# STorM32_NT_splitter_v10.net
KiCad netlist of a schematic drawn in EAGLE
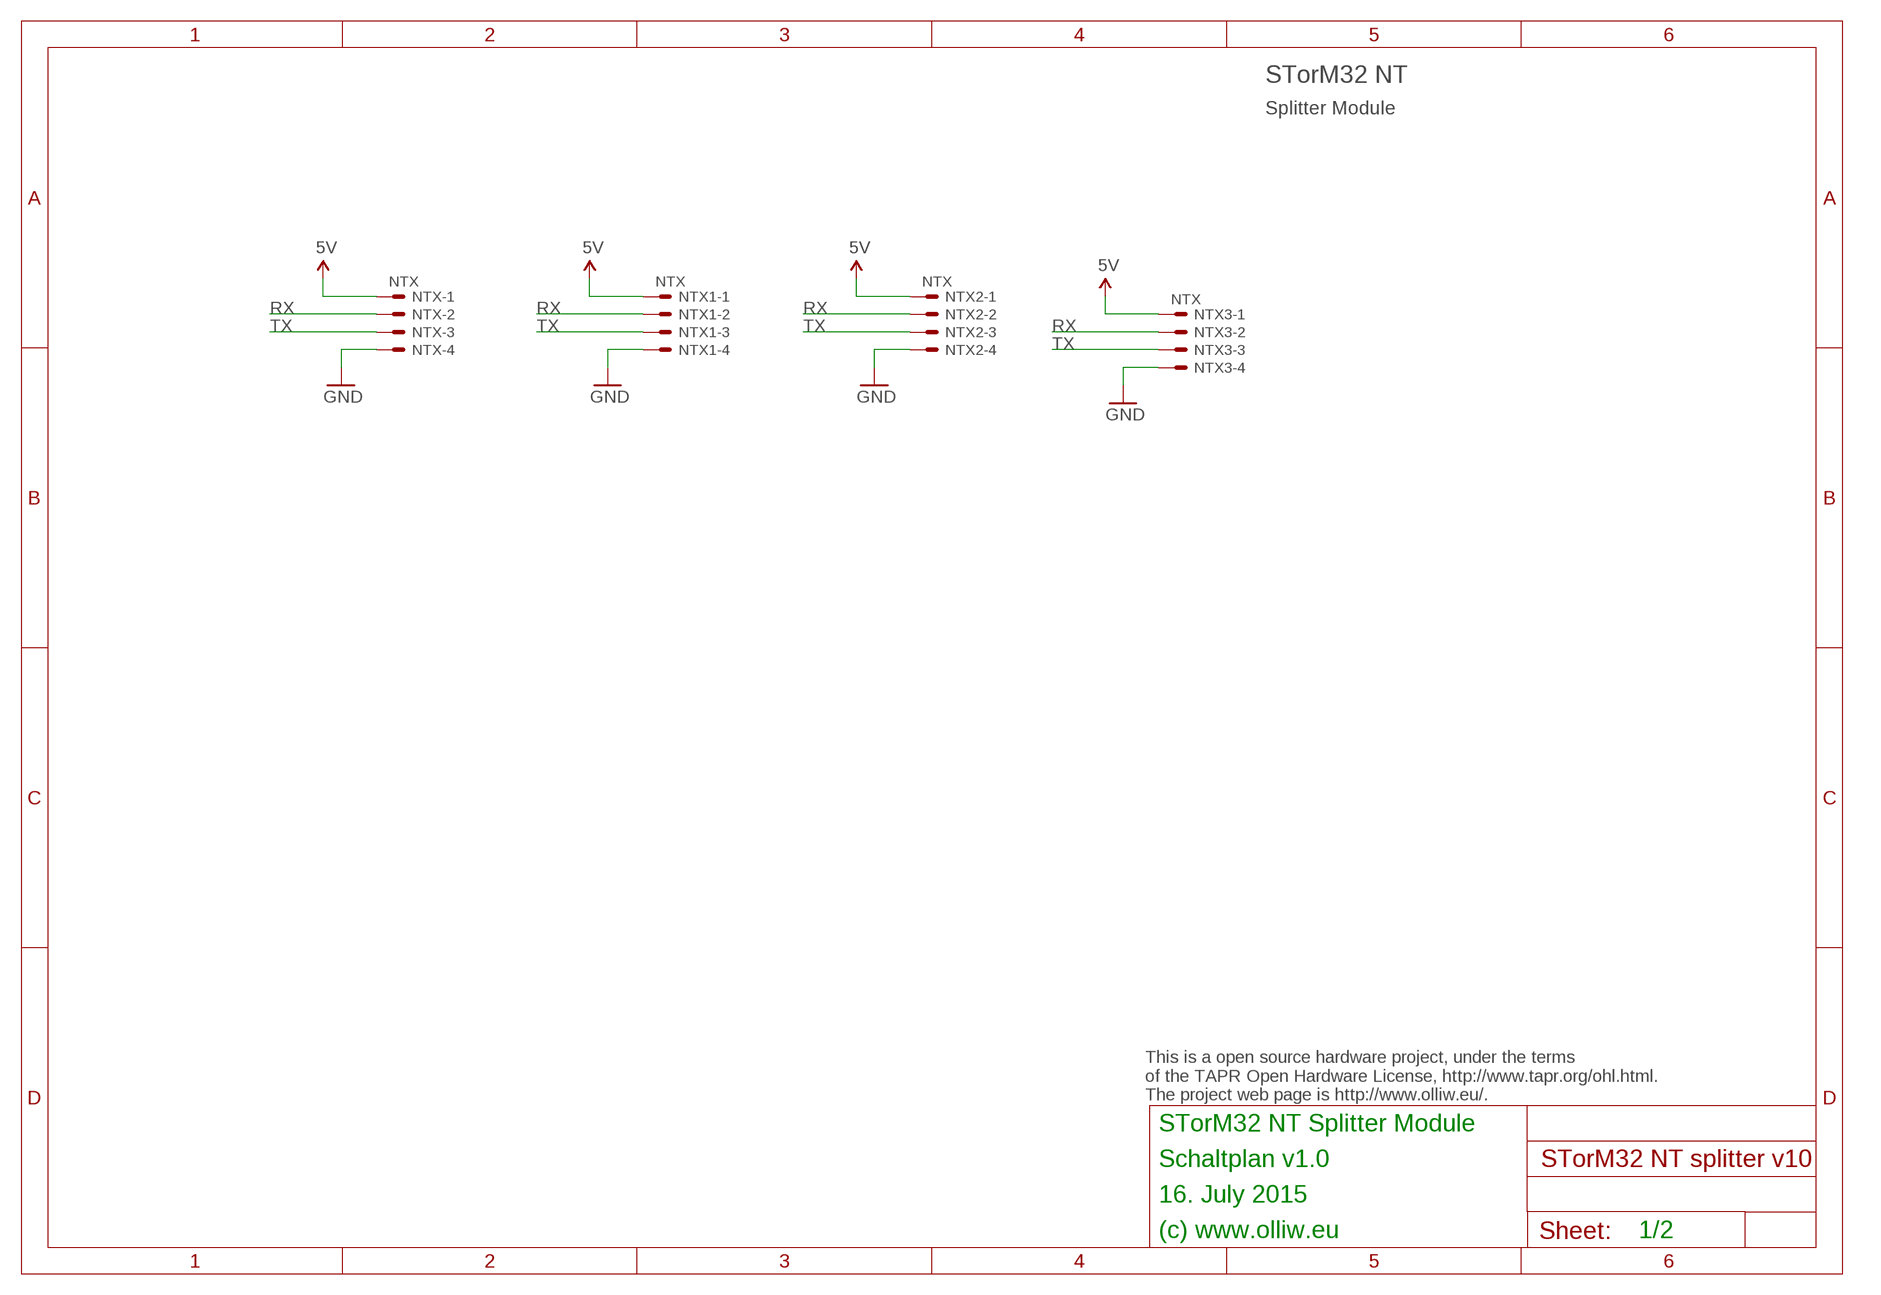
[diagram p0: schematic, sheet 1]

(export (version "E")
  (design (tool "Eeschema 10.0.6"))
  (components
    (comp (ref "NTX")
      (value "NTX")
      (footprint "eagle-import:SM04B-SRSS-TB")
      (libsource (lib "eagle-import") (part "?M04B-SRSS-TBS"))
    )
    (comp (ref "NTX1")
      (value "NTX")
      (footprint "eagle-import:SM04B-SRSS-TB")
      (libsource (lib "eagle-import") (part "?M04B-SRSS-TBS"))
    )
    (comp (ref "NTX2")
      (value "NTX")
      (footprint "eagle-import:SM04B-SRSS-TB")
      (libsource (lib "eagle-import") (part "?M04B-SRSS-TBS"))
    )
    (comp (ref "NTX3")
      (value "NTX")
      (footprint "eagle-import:SM04B-SRSS-TB")
      (libsource (lib "eagle-import") (part "?M04B-SRSS-TBS"))
    )
  )
  (nets
    (net (code "1") (name "/RX") (class "Default")
      (node (ref "NTX") (pin "2") (pinfunction "S_2") (pintype "passive"))
      (node (ref "NTX1") (pin "2") (pinfunction "S_2") (pintype "passive"))
      (node (ref "NTX2") (pin "2") (pinfunction "S_2") (pintype "passive"))
      (node (ref "NTX3") (pin "2") (pinfunction "S_2") (pintype "passive"))
    )
    (net (code "2") (name "/TX") (class "Default")
      (node (ref "NTX") (pin "3") (pinfunction "S_3") (pintype "passive"))
      (node (ref "NTX1") (pin "3") (pinfunction "S_3") (pintype "passive"))
      (node (ref "NTX2") (pin "3") (pinfunction "S_3") (pintype "passive"))
      (node (ref "NTX3") (pin "3") (pinfunction "S_3") (pintype "passive"))
    )
    (net (code "3") (name "5V") (class "Default")
      (node (ref "NTX") (pin "1") (pinfunction "S_1") (pintype "passive"))
      (node (ref "NTX1") (pin "1") (pinfunction "S_1") (pintype "passive"))
      (node (ref "NTX2") (pin "1") (pinfunction "S_1") (pintype "passive"))
      (node (ref "NTX3") (pin "1") (pinfunction "S_1") (pintype "passive"))
    )
    (net (code "4") (name "GND") (class "Default")
      (node (ref "NTX") (pin "4") (pinfunction "S_4") (pintype "passive"))
      (node (ref "NTX1") (pin "4") (pinfunction "S_4") (pintype "passive"))
      (node (ref "NTX2") (pin "4") (pinfunction "S_4") (pintype "passive"))
      (node (ref "NTX3") (pin "4") (pinfunction "S_4") (pintype "passive"))
    )
  )
)
